# untitled.net
KiCad netlist of a schematic drawn in EAGLE
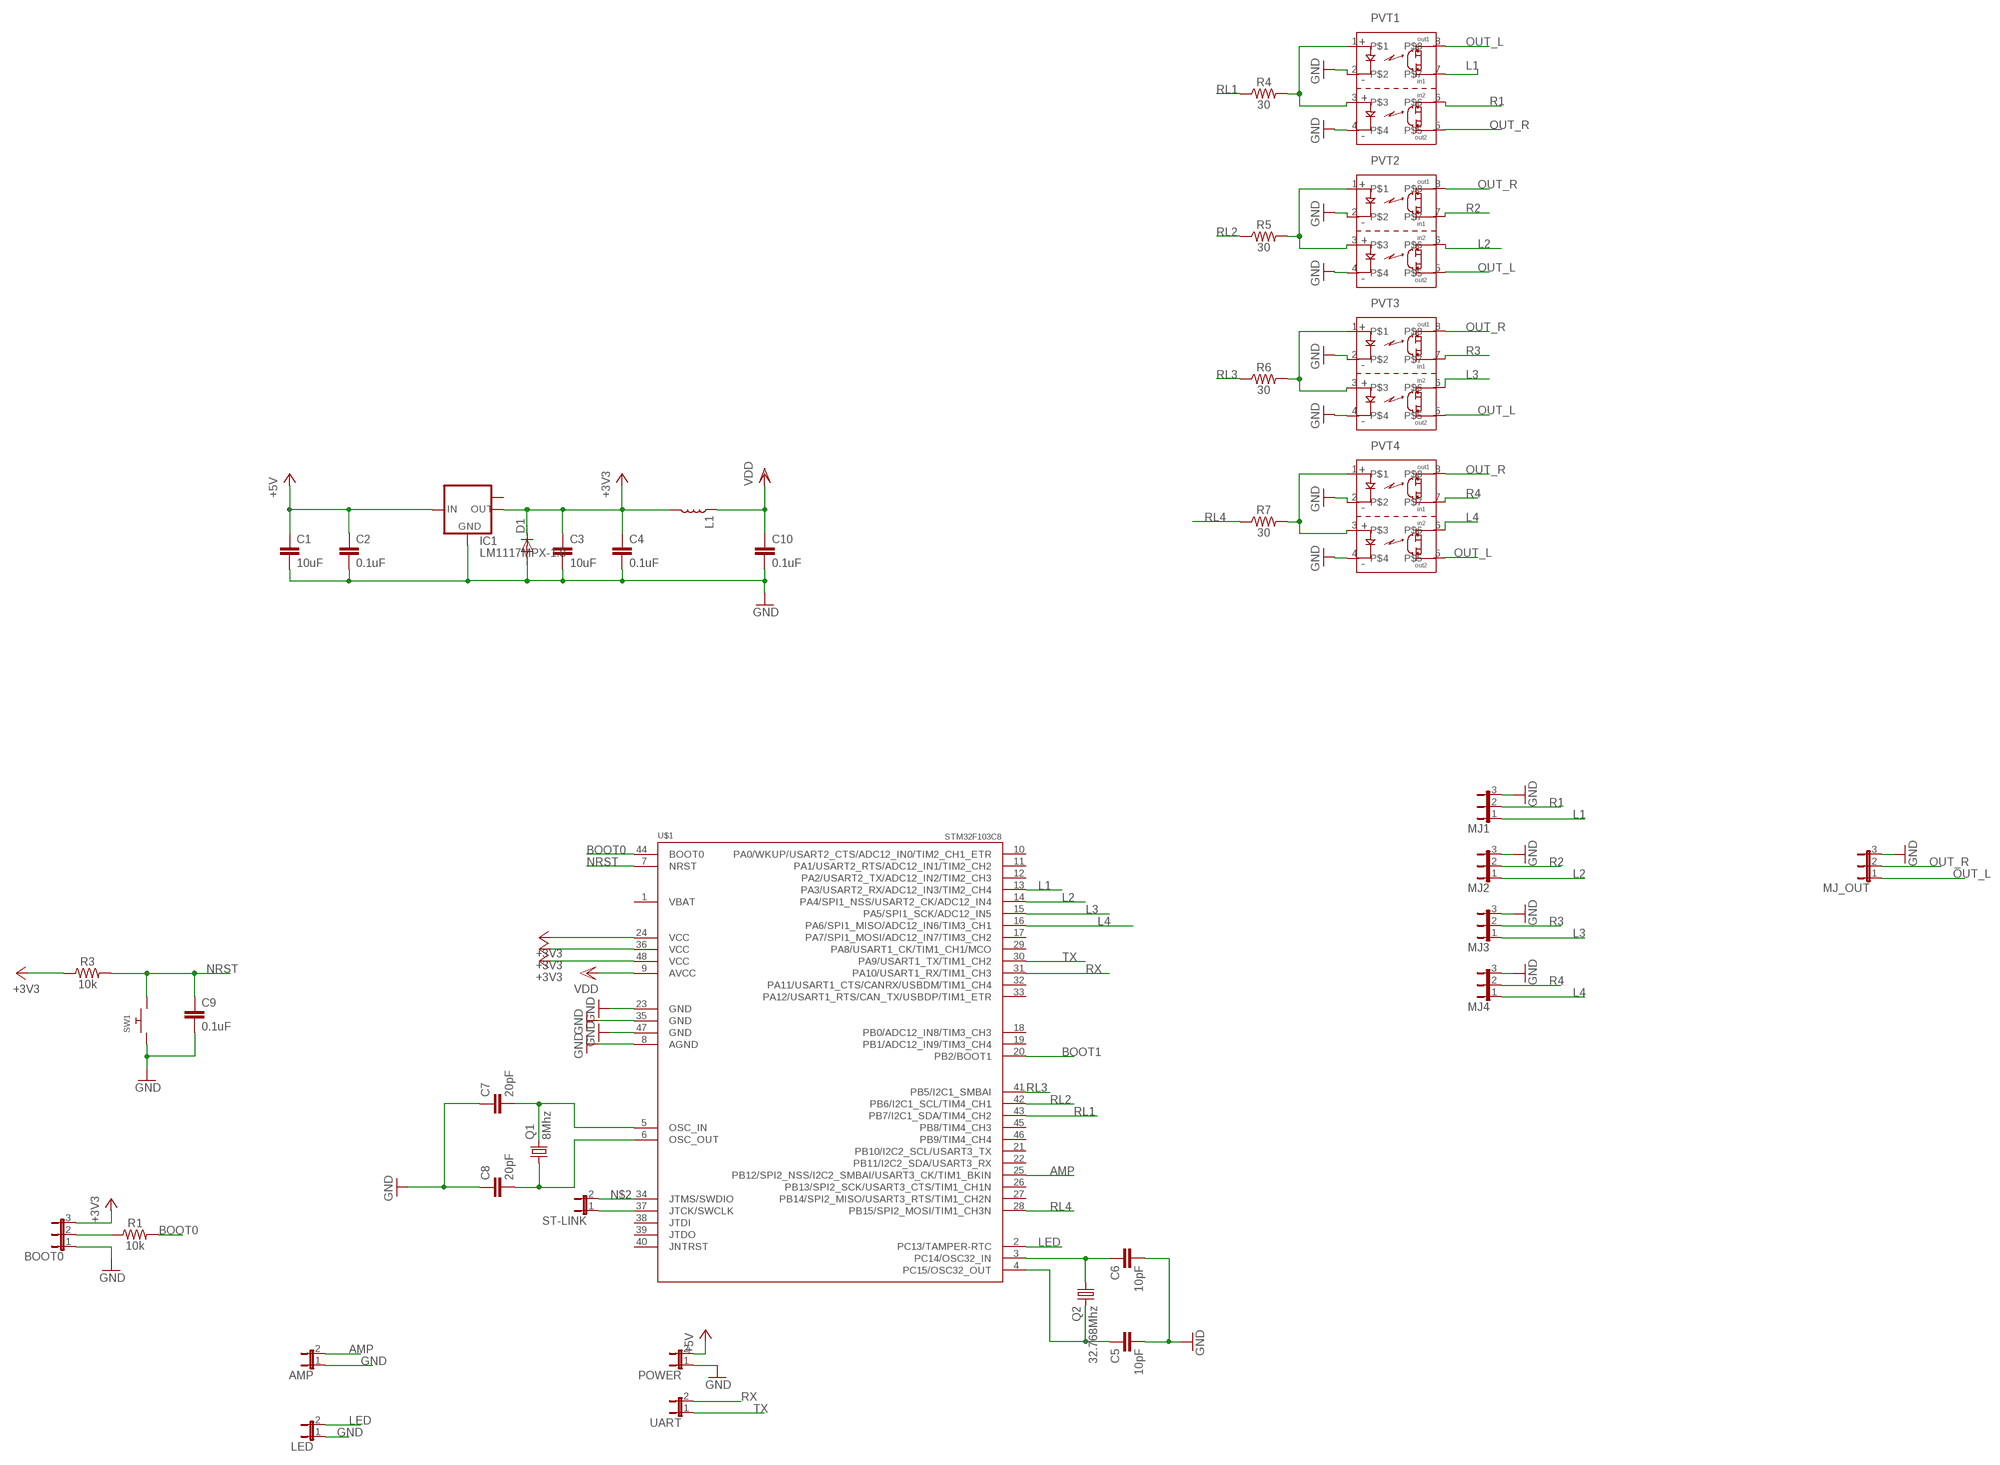
[diagram p0: schematic, sheet 1]

(export (version "E")
  (design (tool "Eeschema 10.0.6"))
  (components
    (comp (ref "AMP")
      (value "JP1E")
      (footprint "eagle-import:JP1")
      (libsource (lib "eagle-import") (part "JP1E"))
    )
    (comp (ref "BOOT0")
      (value "JP2E")
      (footprint "eagle-import:JP2")
      (libsource (lib "eagle-import") (part "JP2E"))
    )
    (comp (ref "C1")
      (value "10uF")
      (footprint "eagle-import:0805")
      (libsource (lib "eagle-import") (part "10UF-0805-10V-10%"))
    )
    (comp (ref "C2")
      (value "0.1uF")
      (footprint "eagle-import:0805")
      (libsource (lib "eagle-import") (part "10UF-0805-10V-10%"))
    )
    (comp (ref "C3")
      (value "10uF")
      (footprint "eagle-import:0805")
      (libsource (lib "eagle-import") (part "10UF-0805-10V-10%"))
    )
    (comp (ref "C4")
      (value "0.1uF")
      (footprint "eagle-import:0805")
      (libsource (lib "eagle-import") (part "10UF-0805-10V-10%"))
    )
    (comp (ref "C5")
      (value "10pF")
      (footprint "eagle-import:0805")
      (libsource (lib "eagle-import") (part "0.33UF/330NF-0805-50V-10%"))
    )
    (comp (ref "C6")
      (value "10pF")
      (footprint "eagle-import:0805")
      (libsource (lib "eagle-import") (part "0.33UF/330NF-0805-50V-10%"))
    )
    (comp (ref "C7")
      (value "20pF")
      (footprint "eagle-import:0805")
      (libsource (lib "eagle-import") (part "0.33UF/330NF-0805-50V-10%"))
    )
    (comp (ref "C8")
      (value "20pF")
      (footprint "eagle-import:0805")
      (libsource (lib "eagle-import") (part "0.33UF/330NF-0805-50V-10%"))
    )
    (comp (ref "C9")
      (value "0.1uF")
      (footprint "eagle-import:0805")
      (libsource (lib "eagle-import") (part "10UF-0805-10V-10%"))
    )
    (comp (ref "C10")
      (value "0.1uF")
      (footprint "eagle-import:0805")
      (libsource (lib "eagle-import") (part "10UF-0805-10V-10%"))
    )
    (comp (ref "D1")
      (value "DIODE-DO214AA")
      (footprint "eagle-import:DO214AA")
      (libsource (lib "eagle-import") (part "DIODE-DO214AA"))
    )
    (comp (ref "IC1")
      (value "LM1117MPX-1.8")
      (footprint "eagle-import:SOT223")
      (libsource (lib "eagle-import") (part "LM1117MPX-1.8"))
    )
    (comp (ref "L1")
      (value "INDUCTORFB-30OHM")
      (footprint "eagle-import:0603")
      (libsource (lib "eagle-import") (part "INDUCTORFB-30OHM"))
    )
    (comp (ref "LED")
      (value "JP1E")
      (footprint "eagle-import:JP1")
      (libsource (lib "eagle-import") (part "JP1E"))
    )
    (comp (ref "MJ1")
      (value "JP2E")
      (footprint "eagle-import:JP2")
      (libsource (lib "eagle-import") (part "JP2E"))
    )
    (comp (ref "MJ2")
      (value "JP2E")
      (footprint "eagle-import:JP2")
      (libsource (lib "eagle-import") (part "JP2E"))
    )
    (comp (ref "MJ3")
      (value "JP2E")
      (footprint "eagle-import:JP2")
      (libsource (lib "eagle-import") (part "JP2E"))
    )
    (comp (ref "MJ4")
      (value "JP2E")
      (footprint "eagle-import:JP2")
      (libsource (lib "eagle-import") (part "JP2E"))
    )
    (comp (ref "MJ_OUT")
      (value "JP2E")
      (footprint "eagle-import:JP2")
      (libsource (lib "eagle-import") (part "JP2E"))
    )
    (comp (ref "POWER")
      (value "JP1E")
      (footprint "eagle-import:JP1")
      (libsource (lib "eagle-import") (part "JP1E"))
    )
    (comp (ref "PVT1")
      (value "PVT322A")
      (footprint "eagle-import:DIP-8")
      (libsource (lib "eagle-import") (part "PVT322A"))
    )
    (comp (ref "PVT2")
      (value "PVT322A")
      (footprint "eagle-import:DIP-8")
      (libsource (lib "eagle-import") (part "PVT322A"))
    )
    (comp (ref "PVT3")
      (value "PVT322A")
      (footprint "eagle-import:DIP-8")
      (libsource (lib "eagle-import") (part "PVT322A"))
    )
    (comp (ref "PVT4")
      (value "PVT322A")
      (footprint "eagle-import:DIP-8")
      (libsource (lib "eagle-import") (part "PVT322A"))
    )
    (comp (ref "Q1")
      (value "8Mhz")
      (footprint "eagle-import:HC49_S")
      (libsource (lib "eagle-import") (part "CRYSTALHC49S"))
    )
    (comp (ref "Q2")
      (value "32.768Mhz")
      (footprint "eagle-import:HC49_S")
      (libsource (lib "eagle-import") (part "CRYSTALHC49S"))
    )
    (comp (ref "R1")
      (value "10k")
      (footprint "eagle-import:0603")
      (libsource (lib "eagle-import") (part "10KOHM-0603-1/10W-1%"))
    )
    (comp (ref "R3")
      (value "10k")
      (footprint "eagle-import:0603")
      (libsource (lib "eagle-import") (part "10KOHM-0603-1/10W-1%"))
    )
    (comp (ref "R4")
      (value "30")
      (footprint "eagle-import:0603")
      (libsource (lib "eagle-import") (part "10KOHM-0603-1/10W-1%"))
    )
    (comp (ref "R5")
      (value "30")
      (footprint "eagle-import:0603")
      (libsource (lib "eagle-import") (part "10KOHM-0603-1/10W-1%"))
    )
    (comp (ref "R6")
      (value "30")
      (footprint "eagle-import:0603")
      (libsource (lib "eagle-import") (part "10KOHM-0603-1/10W-1%"))
    )
    (comp (ref "R7")
      (value "30")
      (footprint "eagle-import:0603")
      (libsource (lib "eagle-import") (part "10KOHM-0603-1/10W-1%"))
    )
    (comp (ref "ST-LINK")
      (value "JP1E")
      (footprint "eagle-import:JP1")
      (libsource (lib "eagle-import") (part "JP1E"))
    )
    (comp (ref "SW1")
      (value "SWITCH_PUSHBUTTONEVQ-PE")
      (footprint "eagle-import:TACT_PANA-EVQ")
      (libsource (lib "eagle-import") (part "SWITCH_PUSHBUTTONEVQ-PE"))
    )
    (comp (ref "U$1")
      (value "STM32F103C8")
      (footprint "eagle-import:LQFP48-7X7")
      (libsource (lib "eagle-import") (part "STM32F103C8"))
    )
    (comp (ref "UART")
      (value "JP1E")
      (footprint "eagle-import:JP1")
      (libsource (lib "eagle-import") (part "JP1E"))
    )
  )
  (nets
    (net (code "1") (name "+3V3") (class "Default")
      (node (ref "BOOT0") (pin "3") (pinfunction "3_3") (pintype "passive"))
      (node (ref "C3") (pin "1") (pinfunction "1_1") (pintype "passive"))
      (node (ref "C4") (pin "1") (pinfunction "1_1") (pintype "passive"))
      (node (ref "D1") (pin "C") (pinfunction "C_C") (pintype "passive"))
      (node (ref "IC1") (pin "2") (pinfunction "OUT_2") (pintype "passive"))
      (node (ref "L1") (pin "2") (pinfunction "2_2") (pintype "passive"))
      (node (ref "R3") (pin "1") (pinfunction "1_1") (pintype "passive"))
      (node (ref "U$1") (pin "24") (pinfunction "VCC_24") (pintype "power_in"))
      (node (ref "U$1") (pin "36") (pinfunction "VCC_36") (pintype "power_in"))
      (node (ref "U$1") (pin "48") (pinfunction "VCC_48") (pintype "power_in"))
    )
    (net (code "2") (name "+5V") (class "Default")
      (node (ref "C1") (pin "1") (pinfunction "1_1") (pintype "passive"))
      (node (ref "C2") (pin "1") (pinfunction "1_1") (pintype "passive"))
      (node (ref "IC1") (pin "3") (pinfunction "IN_3") (pintype "input"))
      (node (ref "POWER") (pin "2") (pinfunction "2_2") (pintype "passive"))
    )
    (net (code "3") (name "/AMP") (class "Default")
      (node (ref "AMP") (pin "2") (pinfunction "2_2") (pintype "passive"))
      (node (ref "U$1") (pin "25") (pinfunction "PB12/SPI2_NSS/I2C2_SMBAI/USART3_CK/TIM1_BKIN_25") (pintype "bidirectional"))
    )
    (net (code "4") (name "/BOOT0") (class "Default")
      (node (ref "R1") (pin "2") (pinfunction "2_2") (pintype "passive"))
      (node (ref "U$1") (pin "44") (pinfunction "BOOT0_44") (pintype "bidirectional"))
    )
    (net (code "5") (name "/BOOT1") (class "Default")
      (node (ref "U$1") (pin "20") (pinfunction "PB2/BOOT1_20") (pintype "bidirectional"))
    )
    (net (code "6") (name "/L1") (class "Default")
      (node (ref "MJ1") (pin "1") (pinfunction "1_1") (pintype "passive"))
      (node (ref "PVT1") (pin "7") (pinfunction "P$7_7") (pintype "bidirectional"))
      (node (ref "U$1") (pin "13") (pinfunction "PA3/USART2_RX/ADC12_IN3/TIM2_CH4_13") (pintype "bidirectional"))
    )
    (net (code "7") (name "/L2") (class "Default")
      (node (ref "MJ2") (pin "1") (pinfunction "1_1") (pintype "passive"))
      (node (ref "PVT2") (pin "6") (pinfunction "P$6_6") (pintype "bidirectional"))
      (node (ref "U$1") (pin "14") (pinfunction "PA4/SPI1_NSS/USART2_CK/ADC12_IN4_14") (pintype "bidirectional"))
    )
    (net (code "8") (name "/L3") (class "Default")
      (node (ref "MJ3") (pin "1") (pinfunction "1_1") (pintype "passive"))
      (node (ref "PVT3") (pin "6") (pinfunction "P$6_6") (pintype "bidirectional"))
      (node (ref "U$1") (pin "15") (pinfunction "PA5/SPI1_SCK/ADC12_IN5_15") (pintype "bidirectional"))
    )
    (net (code "9") (name "/L4") (class "Default")
      (node (ref "MJ4") (pin "1") (pinfunction "1_1") (pintype "passive"))
      (node (ref "PVT4") (pin "6") (pinfunction "P$6_6") (pintype "bidirectional"))
      (node (ref "U$1") (pin "16") (pinfunction "PA6/SPI1_MISO/ADC12_IN6/TIM3_CH1_16") (pintype "bidirectional"))
    )
    (net (code "10") (name "/LED") (class "Default")
      (node (ref "LED") (pin "2") (pinfunction "2_2") (pintype "passive"))
      (node (ref "U$1") (pin "2") (pinfunction "PC13/TAMPER-RTC_2") (pintype "bidirectional"))
    )
    (net (code "11") (name "/N$2") (class "Default")
      (node (ref "ST-LINK") (pin "2") (pinfunction "2_2") (pintype "passive"))
      (node (ref "U$1") (pin "34") (pinfunction "JTMS/SWDIO_34") (pintype "bidirectional"))
    )
    (net (code "12") (name "/NRST") (class "Default")
      (node (ref "C9") (pin "1") (pinfunction "1_1") (pintype "passive"))
      (node (ref "R3") (pin "2") (pinfunction "2_2") (pintype "passive"))
      (node (ref "SW1") (pin "P$2") (pinfunction "P$2_P$2") (pintype "passive"))
      (node (ref "U$1") (pin "7") (pinfunction "NRST_7") (pintype "bidirectional"))
    )
    (net (code "13") (name "/OUT_L") (class "Default")
      (node (ref "MJ_OUT") (pin "1") (pinfunction "1_1") (pintype "passive"))
      (node (ref "PVT1") (pin "8") (pinfunction "P$8_8") (pintype "bidirectional"))
      (node (ref "PVT2") (pin "5") (pinfunction "P$5_5") (pintype "bidirectional"))
      (node (ref "PVT3") (pin "5") (pinfunction "P$5_5") (pintype "bidirectional"))
      (node (ref "PVT4") (pin "5") (pinfunction "P$5_5") (pintype "bidirectional"))
    )
    (net (code "14") (name "/OUT_R") (class "Default")
      (node (ref "MJ_OUT") (pin "2") (pinfunction "2_2") (pintype "passive"))
      (node (ref "PVT1") (pin "5") (pinfunction "P$5_5") (pintype "bidirectional"))
      (node (ref "PVT2") (pin "8") (pinfunction "P$8_8") (pintype "bidirectional"))
      (node (ref "PVT3") (pin "8") (pinfunction "P$8_8") (pintype "bidirectional"))
      (node (ref "PVT4") (pin "8") (pinfunction "P$8_8") (pintype "bidirectional"))
    )
    (net (code "15") (name "/R1") (class "Default")
      (node (ref "MJ1") (pin "2") (pinfunction "2_2") (pintype "passive"))
      (node (ref "PVT1") (pin "6") (pinfunction "P$6_6") (pintype "bidirectional"))
    )
    (net (code "16") (name "/R2") (class "Default")
      (node (ref "MJ2") (pin "2") (pinfunction "2_2") (pintype "passive"))
      (node (ref "PVT2") (pin "7") (pinfunction "P$7_7") (pintype "bidirectional"))
    )
    (net (code "17") (name "/R3") (class "Default")
      (node (ref "MJ3") (pin "2") (pinfunction "2_2") (pintype "passive"))
      (node (ref "PVT3") (pin "7") (pinfunction "P$7_7") (pintype "bidirectional"))
    )
    (net (code "18") (name "/R4") (class "Default")
      (node (ref "MJ4") (pin "2") (pinfunction "2_2") (pintype "passive"))
      (node (ref "PVT4") (pin "7") (pinfunction "P$7_7") (pintype "bidirectional"))
    )
    (net (code "19") (name "/RL1") (class "Default")
      (node (ref "R4") (pin "1") (pinfunction "1_1") (pintype "passive"))
      (node (ref "U$1") (pin "43") (pinfunction "PB7/I2C1_SDA/TIM4_CH2_43") (pintype "bidirectional"))
    )
    (net (code "20") (name "/RL2") (class "Default")
      (node (ref "R5") (pin "1") (pinfunction "1_1") (pintype "passive"))
      (node (ref "U$1") (pin "42") (pinfunction "PB6/I2C1_SCL/TIM4_CH1_42") (pintype "bidirectional"))
    )
    (net (code "21") (name "/RL3") (class "Default")
      (node (ref "R6") (pin "1") (pinfunction "1_1") (pintype "passive"))
      (node (ref "U$1") (pin "41") (pinfunction "PB5/I2C1_SMBAI_41") (pintype "bidirectional"))
    )
    (net (code "22") (name "/RL4") (class "Default")
      (node (ref "R7") (pin "1") (pinfunction "1_1") (pintype "passive"))
      (node (ref "U$1") (pin "28") (pinfunction "PB15/SPI2_MOSI/TIM1_CH3N_28") (pintype "bidirectional"))
    )
    (net (code "23") (name "/RX") (class "Default")
      (node (ref "U$1") (pin "31") (pinfunction "PA10/USART1_RX/TIM1_CH3_31") (pintype "bidirectional"))
      (node (ref "UART") (pin "2") (pinfunction "2_2") (pintype "passive"))
    )
    (net (code "24") (name "/TX") (class "Default")
      (node (ref "U$1") (pin "30") (pinfunction "PA9/USART1_TX/TIM1_CH2_30") (pintype "bidirectional"))
      (node (ref "UART") (pin "1") (pinfunction "1_1") (pintype "passive"))
    )
    (net (code "25") (name "/VBAT") (class "Default")
      (node (ref "U$1") (pin "1") (pinfunction "VBAT_1") (pintype "power_in"))
    )
    (net (code "26") (name "GND") (class "Default")
      (node (ref "AMP") (pin "1") (pinfunction "1_1") (pintype "passive"))
      (node (ref "BOOT0") (pin "1") (pinfunction "1_1") (pintype "passive"))
      (node (ref "C1") (pin "2") (pinfunction "2_2") (pintype "passive"))
      (node (ref "C10") (pin "2") (pinfunction "2_2") (pintype "passive"))
      (node (ref "C2") (pin "2") (pinfunction "2_2") (pintype "passive"))
      (node (ref "C3") (pin "2") (pinfunction "2_2") (pintype "passive"))
      (node (ref "C4") (pin "2") (pinfunction "2_2") (pintype "passive"))
      (node (ref "C5") (pin "2") (pinfunction "2_2") (pintype "passive"))
      (node (ref "C6") (pin "2") (pinfunction "2_2") (pintype "passive"))
      (node (ref "C7") (pin "1") (pinfunction "1_1") (pintype "passive"))
      (node (ref "C8") (pin "1") (pinfunction "1_1") (pintype "passive"))
      (node (ref "C9") (pin "2") (pinfunction "2_2") (pintype "passive"))
      (node (ref "D1") (pin "A") (pinfunction "A_A") (pintype "passive"))
      (node (ref "IC1") (pin "1") (pinfunction "GND_1") (pintype "input"))
      (node (ref "LED") (pin "1") (pinfunction "1_1") (pintype "passive"))
      (node (ref "MJ1") (pin "3") (pinfunction "3_3") (pintype "passive"))
      (node (ref "MJ2") (pin "3") (pinfunction "3_3") (pintype "passive"))
      (node (ref "MJ3") (pin "3") (pinfunction "3_3") (pintype "passive"))
      (node (ref "MJ4") (pin "3") (pinfunction "3_3") (pintype "passive"))
      (node (ref "MJ_OUT") (pin "3") (pinfunction "3_3") (pintype "passive"))
      (node (ref "POWER") (pin "1") (pinfunction "1_1") (pintype "passive"))
      (node (ref "PVT1") (pin "2") (pinfunction "P$2_2") (pintype "bidirectional"))
      (node (ref "PVT1") (pin "4") (pinfunction "P$4_4") (pintype "bidirectional"))
      (node (ref "PVT2") (pin "2") (pinfunction "P$2_2") (pintype "bidirectional"))
      (node (ref "PVT2") (pin "4") (pinfunction "P$4_4") (pintype "bidirectional"))
      (node (ref "PVT3") (pin "2") (pinfunction "P$2_2") (pintype "bidirectional"))
      (node (ref "PVT3") (pin "4") (pinfunction "P$4_4") (pintype "bidirectional"))
      (node (ref "PVT4") (pin "2") (pinfunction "P$2_2") (pintype "bidirectional"))
      (node (ref "PVT4") (pin "4") (pinfunction "P$4_4") (pintype "bidirectional"))
      (node (ref "SW1") (pin "P$1") (pinfunction "P$1_P$1") (pintype "passive"))
      (node (ref "U$1") (pin "23") (pinfunction "GND_23") (pintype "power_in"))
      (node (ref "U$1") (pin "35") (pinfunction "GND_35") (pintype "power_in"))
      (node (ref "U$1") (pin "47") (pinfunction "GND_47") (pintype "power_in"))
      (node (ref "U$1") (pin "8") (pinfunction "AGND_8") (pintype "power_in"))
    )
    (net (code "27") (name "Net-(BOOT0-Pad2)") (class "Default")
      (node (ref "BOOT0") (pin "2") (pinfunction "2_2") (pintype "passive"))
      (node (ref "R1") (pin "1") (pinfunction "1_1") (pintype "passive"))
    )
    (net (code "28") (name "Net-(PVT1-P$1)") (class "Default")
      (node (ref "PVT1") (pin "1") (pinfunction "P$1_1") (pintype "bidirectional"))
      (node (ref "PVT1") (pin "3") (pinfunction "P$3_3") (pintype "bidirectional"))
      (node (ref "R4") (pin "2") (pinfunction "2_2") (pintype "passive"))
    )
    (net (code "29") (name "Net-(PVT2-P$1)") (class "Default")
      (node (ref "PVT2") (pin "1") (pinfunction "P$1_1") (pintype "bidirectional"))
      (node (ref "PVT2") (pin "3") (pinfunction "P$3_3") (pintype "bidirectional"))
      (node (ref "R5") (pin "2") (pinfunction "2_2") (pintype "passive"))
    )
    (net (code "30") (name "Net-(PVT3-P$1)") (class "Default")
      (node (ref "PVT3") (pin "1") (pinfunction "P$1_1") (pintype "bidirectional"))
      (node (ref "PVT3") (pin "3") (pinfunction "P$3_3") (pintype "bidirectional"))
      (node (ref "R6") (pin "2") (pinfunction "2_2") (pintype "passive"))
    )
    (net (code "31") (name "Net-(PVT4-P$1)") (class "Default")
      (node (ref "PVT4") (pin "1") (pinfunction "P$1_1") (pintype "bidirectional"))
      (node (ref "PVT4") (pin "3") (pinfunction "P$3_3") (pintype "bidirectional"))
      (node (ref "R7") (pin "2") (pinfunction "2_2") (pintype "passive"))
    )
    (net (code "32") (name "Net-(U$1-JTCK{slash}SWCLK)") (class "Default")
      (node (ref "ST-LINK") (pin "1") (pinfunction "1_1") (pintype "passive"))
      (node (ref "U$1") (pin "37") (pinfunction "JTCK/SWCLK_37") (pintype "bidirectional"))
    )
    (net (code "33") (name "Net-(U$1-OSC_IN)") (class "Default")
      (node (ref "C7") (pin "2") (pinfunction "2_2") (pintype "passive"))
      (node (ref "Q1") (pin "2") (pinfunction "2_2") (pintype "passive"))
      (node (ref "U$1") (pin "5") (pinfunction "OSC_IN_5") (pintype "input"))
    )
    (net (code "34") (name "Net-(U$1-OSC_OUT)") (class "Default")
      (node (ref "C8") (pin "2") (pinfunction "2_2") (pintype "passive"))
      (node (ref "Q1") (pin "1") (pinfunction "1_1") (pintype "passive"))
      (node (ref "U$1") (pin "6") (pinfunction "OSC_OUT_6") (pintype "output"))
    )
    (net (code "35") (name "Net-(U$1-PC14{slash}OSC32_IN)") (class "Default")
      (node (ref "C6") (pin "1") (pinfunction "1_1") (pintype "passive"))
      (node (ref "Q2") (pin "1") (pinfunction "1_1") (pintype "passive"))
      (node (ref "U$1") (pin "3") (pinfunction "PC14/OSC32_IN_3") (pintype "bidirectional"))
    )
    (net (code "36") (name "Net-(U$1-PC15{slash}OSC32_OUT)") (class "Default")
      (node (ref "C5") (pin "1") (pinfunction "1_1") (pintype "passive"))
      (node (ref "Q2") (pin "2") (pinfunction "2_2") (pintype "passive"))
      (node (ref "U$1") (pin "4") (pinfunction "PC15/OSC32_OUT_4") (pintype "bidirectional"))
    )
    (net (code "37") (name "VDD") (class "Default")
      (node (ref "C10") (pin "1") (pinfunction "1_1") (pintype "passive"))
      (node (ref "L1") (pin "1") (pinfunction "1_1") (pintype "passive"))
      (node (ref "U$1") (pin "9") (pinfunction "AVCC_9") (pintype "power_in"))
    )
    (net (code "38") (name "unconnected-(IC1-OUT1-PadTAB)") (class "Default")
      (node (ref "IC1") (pin "TAB") (pinfunction "OUT1_TAB") (pintype "passive"))
    )
    (net (code "39") (name "unconnected-(U$1-JNTRST-Pad40)") (class "Default")
      (node (ref "U$1") (pin "40") (pinfunction "JNTRST_40") (pintype "bidirectional"))
    )
    (net (code "40") (name "unconnected-(U$1-JTDI-Pad38)") (class "Default")
      (node (ref "U$1") (pin "38") (pinfunction "JTDI_38") (pintype "bidirectional"))
    )
    (net (code "41") (name "unconnected-(U$1-JTDO-Pad39)") (class "Default")
      (node (ref "U$1") (pin "39") (pinfunction "JTDO_39") (pintype "bidirectional"))
    )
    (net (code "42") (name "unconnected-(U$1-PA0{slash}WKUP{slash}USART2_CTS{slash}ADC12_IN0{slash}TIM2_CH1_ETR-Pad10)") (class "Default")
      (node (ref "U$1") (pin "10") (pinfunction "PA0/WKUP/USART2_CTS/ADC12_IN0/TIM2_CH1_ETR_10") (pintype "bidirectional"))
    )
    (net (code "43") (name "unconnected-(U$1-PA1{slash}USART2_RTS{slash}ADC12_IN1{slash}TIM2_CH2-Pad11)") (class "Default")
      (node (ref "U$1") (pin "11") (pinfunction "PA1/USART2_RTS/ADC12_IN1/TIM2_CH2_11") (pintype "bidirectional"))
    )
    (net (code "44") (name "unconnected-(U$1-PA2{slash}USART2_TX{slash}ADC12_IN2{slash}TIM2_CH3-Pad12)") (class "Default")
      (node (ref "U$1") (pin "12") (pinfunction "PA2/USART2_TX/ADC12_IN2/TIM2_CH3_12") (pintype "bidirectional"))
    )
    (net (code "45") (name "unconnected-(U$1-PA7{slash}SPI1_MOSI{slash}ADC12_IN7{slash}TIM3_CH2-Pad17)") (class "Default")
      (node (ref "U$1") (pin "17") (pinfunction "PA7/SPI1_MOSI/ADC12_IN7/TIM3_CH2_17") (pintype "bidirectional"))
    )
    (net (code "46") (name "unconnected-(U$1-PA8{slash}USART1_CK{slash}TIM1_CH1{slash}MCO-Pad29)") (class "Default")
      (node (ref "U$1") (pin "29") (pinfunction "PA8/USART1_CK/TIM1_CH1/MCO_29") (pintype "bidirectional"))
    )
    (net (code "47") (name "unconnected-(U$1-PA11{slash}USART1_CTS{slash}CANRX{slash}USBDM{slash}TIM1_CH4-Pad32)") (class "Default")
      (node (ref "U$1") (pin "32") (pinfunction "PA11/USART1_CTS/CANRX/USBDM/TIM1_CH4_32") (pintype "bidirectional"))
    )
    (net (code "48") (name "unconnected-(U$1-PA12{slash}USART1_RTS{slash}CAN_TX{slash}USBDP{slash}TIM1_ETR-Pad33)") (class "Default")
      (node (ref "U$1") (pin "33") (pinfunction "PA12/USART1_RTS/CAN_TX/USBDP/TIM1_ETR_33") (pintype "bidirectional"))
    )
    (net (code "49") (name "unconnected-(U$1-PB0{slash}ADC12_IN8{slash}TIM3_CH3-Pad18)") (class "Default")
      (node (ref "U$1") (pin "18") (pinfunction "PB0/ADC12_IN8/TIM3_CH3_18") (pintype "bidirectional"))
    )
    (net (code "50") (name "unconnected-(U$1-PB1{slash}ADC12_IN9{slash}TIM3_CH4-Pad19)") (class "Default")
      (node (ref "U$1") (pin "19") (pinfunction "PB1/ADC12_IN9/TIM3_CH4_19") (pintype "bidirectional"))
    )
    (net (code "51") (name "unconnected-(U$1-PB8{slash}TIM4_CH3-Pad45)") (class "Default")
      (node (ref "U$1") (pin "45") (pinfunction "PB8/TIM4_CH3_45") (pintype "bidirectional"))
    )
    (net (code "52") (name "unconnected-(U$1-PB9{slash}TIM4_CH4-Pad46)") (class "Default")
      (node (ref "U$1") (pin "46") (pinfunction "PB9/TIM4_CH4_46") (pintype "bidirectional"))
    )
    (net (code "53") (name "unconnected-(U$1-PB10{slash}I2C2_SCL{slash}USART3_TX-Pad21)") (class "Default")
      (node (ref "U$1") (pin "21") (pinfunction "PB10/I2C2_SCL/USART3_TX_21") (pintype "bidirectional"))
    )
    (net (code "54") (name "unconnected-(U$1-PB11{slash}I2C2_SDA{slash}USART3_RX-Pad22)") (class "Default")
      (node (ref "U$1") (pin "22") (pinfunction "PB11/I2C2_SDA/USART3_RX_22") (pintype "bidirectional"))
    )
    (net (code "55") (name "unconnected-(U$1-PB13{slash}SPI2_SCK{slash}USART3_CTS{slash}TIM1_CH1N-Pad26)") (class "Default")
      (node (ref "U$1") (pin "26") (pinfunction "PB13/SPI2_SCK/USART3_CTS/TIM1_CH1N_26") (pintype "bidirectional"))
    )
    (net (code "56") (name "unconnected-(U$1-PB14{slash}SPI2_MISO{slash}USART3_RTS{slash}TIM1_CH2N-Pad27)") (class "Default")
      (node (ref "U$1") (pin "27") (pinfunction "PB14/SPI2_MISO/USART3_RTS/TIM1_CH2N_27") (pintype "bidirectional"))
    )
  )
)
